# Kill_Switch_Testing.net
KiCad netlist of a schematic drawn in Altium Designer
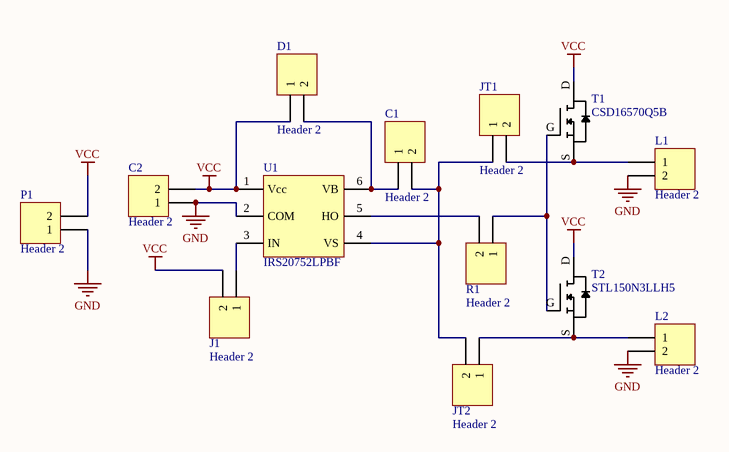
[diagram p0: Kill_Switch_Testing.SchDoc]

(export (version "E")
  (design (tool "Eeschema 10.0.6"))
  (components
    (comp (ref "C1")
      (value "Header 2")
      (footprint "HDR1X2")
      (description "Header, 2-Pin")
      (fields (field (name "PUBLISHER") "Altium Limited"))
      (libsource (lib "") (part "Header 2_1"))
    )
    (comp (ref "C2")
      (value "Header 2")
      (footprint "HDR1X2")
      (description "Header, 2-Pin")
      (fields (field (name "PUBLISHER") "Altium Limited"))
      (libsource (lib "") (part "Header 2_3"))
    )
    (comp (ref "D1")
      (value "Header 2")
      (footprint "HDR1X2")
      (description "Header, 2-Pin")
      (fields (field (name "PUBLISHER") "Altium Limited"))
      (libsource (lib "") (part "Header 2_1"))
    )
    (comp (ref "J1")
      (value "Header 2")
      (footprint "HDR1X2")
      (description "Header, 2-Pin")
      (fields (field (name "PUBLISHER") "Altium Limited"))
      (libsource (lib "") (part "Header 2_2"))
    )
    (comp (ref "JT1")
      (value "Header 2")
      (footprint "HDR1X2")
      (description "Header, 2-Pin")
      (fields (field (name "PUBLISHER") "Altium Limited"))
      (libsource (lib "") (part "Header 2_1"))
    )
    (comp (ref "JT2")
      (value "Header 2")
      (footprint "HDR1X2")
      (description "Header, 2-Pin")
      (fields (field (name "PUBLISHER") "Altium Limited"))
      (libsource (lib "") (part "Header 2_2"))
    )
    (comp (ref "L1")
      (value "Header 2")
      (footprint "HDR1X2")
      (description "Header, 2-Pin")
      (fields (field (name "PUBLISHER") "Altium Limited"))
      (libsource (lib "Miscellaneous Connectors") (part "Header 2"))
    )
    (comp (ref "L2")
      (value "Header 2")
      (footprint "HDR1X2")
      (description "Header, 2-Pin")
      (fields (field (name "PUBLISHER") "Altium Limited"))
      (libsource (lib "Miscellaneous Connectors") (part "Header 2"))
    )
    (comp (ref "P1")
      (value "Header 2")
      (footprint "HDR1X2")
      (description "Header, 2-Pin")
      (fields (field (name "PUBLISHER") "Altium Limited"))
      (libsource (lib "") (part "Header 2_3"))
    )
    (comp (ref "R1")
      (value "Header 2")
      (footprint "HDR1X2")
      (description "Header, 2-Pin")
      (fields (field (name "PUBLISHER") "Altium Limited"))
      (libsource (lib "") (part "Header 2_2"))
    )
    (comp (ref "T1")
      (value "CSD16570Q5B")
      (footprint "CSD16570Q5B")
      (description "25-V N-Channel NexFET™ Power MOSFET")
      (libsource (lib "Kill_Switch_Testing") (part "CSD16570Q5B"))
    )
    (comp (ref "T2")
      (value "STL150N3LLH5")
      (footprint "STL150N3LLH5")
      (description "N-channel 30 V, 0.0014 Ω typ., 35 A STripFET™ V Power MOSFET")
      (libsource (lib "Kill_Switch_Testing") (part "STL150N3LLH5"))
    )
    (comp (ref "U1")
      (value "IRS20752LPBF")
      (footprint "IRS20752LPBF")
      (description "SOT-23 High-Side Gate Driver IC")
      (libsource (lib "Kill_Switch_Testing") (part "IRS20752LPBF"))
    )
  )
  (nets
    (net (code "1") (name "GND") (class "Default")
      (node (ref "C2") (pin "1") (pinfunction "1_1") (pintype "passive"))
      (node (ref "L1") (pin "2") (pinfunction "2_2") (pintype "passive"))
      (node (ref "L2") (pin "2") (pinfunction "2_2") (pintype "passive"))
      (node (ref "P1") (pin "1") (pinfunction "1_1") (pintype "passive"))
      (node (ref "U1") (pin "2") (pinfunction "COM_2") (pintype "passive"))
    )
    (net (code "2") (name "Net-(T1-Gate)") (class "Default")
      (node (ref "R1") (pin "1") (pinfunction "1_1") (pintype "passive"))
      (node (ref "T1") (pin "G") (pinfunction "Gate_G") (pintype "passive"))
      (node (ref "T2") (pin "G") (pinfunction "Gate_G") (pintype "passive"))
    )
    (net (code "3") (name "Net-(T1-Source)") (class "Default")
      (node (ref "JT1") (pin "2") (pinfunction "2_2") (pintype "passive"))
      (node (ref "L1") (pin "1") (pinfunction "1_1") (pintype "passive"))
      (node (ref "T1") (pin "S") (pinfunction "Source_S") (pintype "passive"))
    )
    (net (code "4") (name "Net-(T2-Source)") (class "Default")
      (node (ref "JT2") (pin "1") (pinfunction "1_1") (pintype "passive"))
      (node (ref "L2") (pin "1") (pinfunction "1_1") (pintype "passive"))
      (node (ref "T2") (pin "S") (pinfunction "Source_S") (pintype "passive"))
    )
    (net (code "5") (name "Net-(U1-HO)") (class "Default")
      (node (ref "R1") (pin "2") (pinfunction "2_2") (pintype "passive"))
      (node (ref "U1") (pin "5") (pinfunction "HO_5") (pintype "passive"))
    )
    (net (code "6") (name "Net-(U1-IN)") (class "Default")
      (node (ref "J1") (pin "1") (pinfunction "1_1") (pintype "passive"))
      (node (ref "U1") (pin "3") (pinfunction "IN_3") (pintype "passive"))
    )
    (net (code "7") (name "Net-(U1-VB)") (class "Default")
      (node (ref "C1") (pin "1") (pinfunction "1_1") (pintype "passive"))
      (node (ref "D1") (pin "2") (pinfunction "2_2") (pintype "passive"))
      (node (ref "U1") (pin "6") (pinfunction "VB_6") (pintype "passive"))
    )
    (net (code "8") (name "Net-(U1-VS)") (class "Default")
      (node (ref "C1") (pin "2") (pinfunction "2_2") (pintype "passive"))
      (node (ref "JT1") (pin "1") (pinfunction "1_1") (pintype "passive"))
      (node (ref "JT2") (pin "2") (pinfunction "2_2") (pintype "passive"))
      (node (ref "U1") (pin "4") (pinfunction "VS_4") (pintype "passive"))
    )
    (net (code "9") (name "VCC") (class "Default")
      (node (ref "C2") (pin "2") (pinfunction "2_2") (pintype "passive"))
      (node (ref "D1") (pin "1") (pinfunction "1_1") (pintype "passive"))
      (node (ref "J1") (pin "2") (pinfunction "2_2") (pintype "passive"))
      (node (ref "P1") (pin "2") (pinfunction "2_2") (pintype "passive"))
      (node (ref "T1") (pin "D") (pinfunction "Drain_D") (pintype "passive"))
      (node (ref "T2") (pin "D") (pinfunction "Drain_D") (pintype "passive"))
      (node (ref "U1") (pin "1") (pinfunction "Vcc_1") (pintype "passive"))
    )
  )
)
